# working.net
KiCad netlist of a schematic drawn in EAGLE
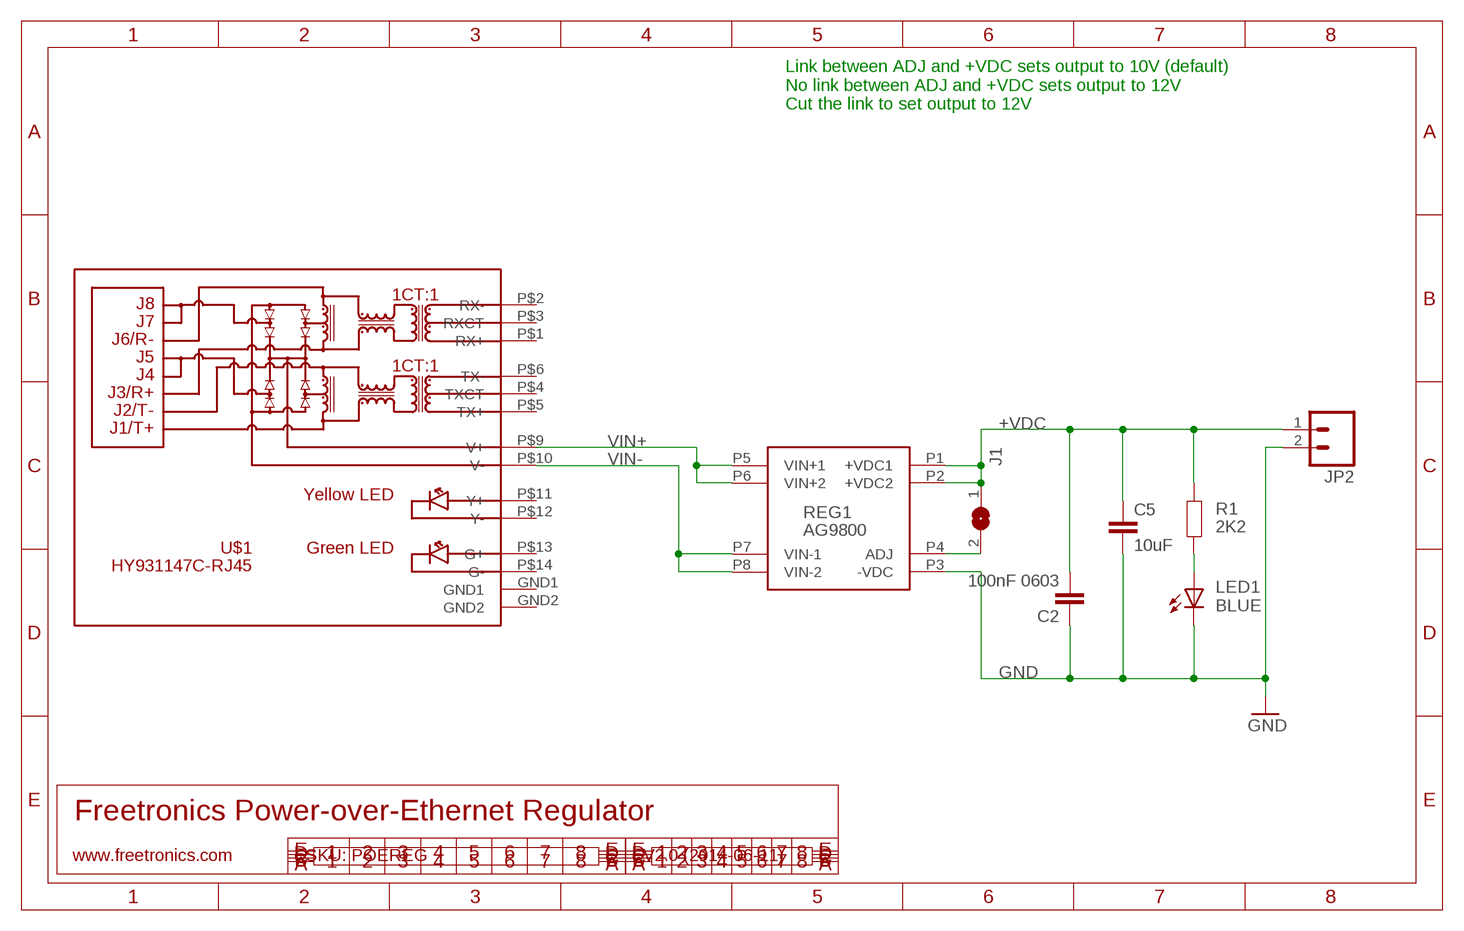
[diagram p0: schematic, sheet 1]

(export (version "E")
  (design (tool "Eeschema 10.0.6"))
  (components
    (comp (ref "C2")
      (value "100nF 0603")
      (footprint "eagle-import:0603")
      (libsource (lib "eagle-import") (part "CAP0603"))
    )
    (comp (ref "C5")
      (value "10uF")
      (footprint "eagle-import:C1206")
      (libsource (lib "eagle-import") (part "C-EUC1206"))
    )
    (comp (ref "J1")
      (value "SJN")
      (footprint "eagle-import:SJ")
      (libsource (lib "eagle-import") (part "SJN"))
    )
    (comp (ref "JP2")
      (value "M025MM")
      (footprint "eagle-import:SCREWTERMINAL-5MM-2")
      (libsource (lib "eagle-import") (part "M025MM"))
    )
    (comp (ref "LED1")
      (value "BLUE")
      (footprint "eagle-import:LED-0603")
      (libsource (lib "eagle-import") (part "LED0603"))
    )
    (comp (ref "R1")
      (value "2K2")
      (footprint "eagle-import:0603")
      (libsource (lib "eagle-import") (part "RESISTOR0603"))
    )
    (comp (ref "REG1")
      (value "AG9800")
      (footprint "eagle-import:AG9800")
      (libsource (lib "eagle-import") (part "AG9800"))
    )
    (comp (ref "U$1")
      (value "HY931147C-RJ45")
      (footprint "eagle-import:HY931147C")
      (libsource (lib "eagle-import") (part "HY931147C-RJ45"))
    )
  )
  (nets
    (net (code "1") (name "/+VDC") (class "Default")
      (node (ref "C2") (pin "2") (pinfunction "2_2") (pintype "passive"))
      (node (ref "C5") (pin "1") (pinfunction "1_1") (pintype "passive"))
      (node (ref "J1") (pin "1") (pinfunction "1_1") (pintype "passive"))
      (node (ref "JP2") (pin "1") (pinfunction "1_1") (pintype "passive"))
      (node (ref "R1") (pin "1") (pinfunction "1_1") (pintype "passive"))
      (node (ref "REG1") (pin "P1") (pinfunction "+VDC1_P1") (pintype "bidirectional"))
      (node (ref "REG1") (pin "P2") (pinfunction "+VDC2_P2") (pintype "bidirectional"))
    )
    (net (code "2") (name "/VIN+") (class "Default")
      (node (ref "REG1") (pin "P5") (pinfunction "VIN+1_P5") (pintype "power_in"))
      (node (ref "REG1") (pin "P6") (pinfunction "VIN+2_P6") (pintype "power_in"))
      (node (ref "U$1") (pin "P$9") (pinfunction "V+_P$9") (pintype "bidirectional"))
    )
    (net (code "3") (name "/VIN-") (class "Default")
      (node (ref "REG1") (pin "P7") (pinfunction "VIN-1_P7") (pintype "power_in"))
      (node (ref "REG1") (pin "P8") (pinfunction "VIN-2_P8") (pintype "power_in"))
      (node (ref "U$1") (pin "P$10") (pinfunction "V-_P$10") (pintype "bidirectional"))
    )
    (net (code "4") (name "GND") (class "Default")
      (node (ref "C2") (pin "1") (pinfunction "1_1") (pintype "passive"))
      (node (ref "C5") (pin "2") (pinfunction "2_2") (pintype "passive"))
      (node (ref "JP2") (pin "2") (pinfunction "2_2") (pintype "passive"))
      (node (ref "LED1") (pin "C") (pinfunction "C_C") (pintype "passive"))
      (node (ref "REG1") (pin "P3") (pinfunction "-VDC_P3") (pintype "bidirectional"))
    )
    (net (code "5") (name "Net-(LED1-PadA)") (class "Default")
      (node (ref "LED1") (pin "A") (pinfunction "A_A") (pintype "passive"))
      (node (ref "R1") (pin "2") (pinfunction "2_2") (pintype "passive"))
    )
    (net (code "6") (name "Net-(REG1-ADJ)") (class "Default")
      (node (ref "J1") (pin "2") (pinfunction "2_2") (pintype "passive"))
      (node (ref "REG1") (pin "P4") (pinfunction "ADJ_P4") (pintype "input"))
    )
    (net (code "7") (name "unconnected-(U$1-G+-PadP$13)") (class "Default")
      (node (ref "U$1") (pin "P$13") (pinfunction "G+_P$13") (pintype "bidirectional"))
    )
    (net (code "8") (name "unconnected-(U$1-G--PadP$14)") (class "Default")
      (node (ref "U$1") (pin "P$14") (pinfunction "G-_P$14") (pintype "bidirectional"))
    )
    (net (code "9") (name "unconnected-(U$1-PadGND1)") (class "Default")
      (node (ref "U$1") (pin "GND1") (pinfunction "GND1_GND1") (pintype "bidirectional"))
    )
    (net (code "10") (name "unconnected-(U$1-PadGND2)") (class "Default")
      (node (ref "U$1") (pin "GND2") (pinfunction "GND2_GND2") (pintype "bidirectional"))
    )
    (net (code "11") (name "unconnected-(U$1-RX+-PadP$1)") (class "Default")
      (node (ref "U$1") (pin "P$1") (pinfunction "RX+_P$1") (pintype "bidirectional"))
    )
    (net (code "12") (name "unconnected-(U$1-RX--PadP$2)") (class "Default")
      (node (ref "U$1") (pin "P$2") (pinfunction "RX-_P$2") (pintype "bidirectional"))
    )
    (net (code "13") (name "unconnected-(U$1-RXCT-PadP$3)") (class "Default")
      (node (ref "U$1") (pin "P$3") (pinfunction "RXCT_P$3") (pintype "bidirectional"))
    )
    (net (code "14") (name "unconnected-(U$1-TX+-PadP$5)") (class "Default")
      (node (ref "U$1") (pin "P$5") (pinfunction "TX+_P$5") (pintype "bidirectional"))
    )
    (net (code "15") (name "unconnected-(U$1-TX--PadP$6)") (class "Default")
      (node (ref "U$1") (pin "P$6") (pinfunction "TX-_P$6") (pintype "bidirectional"))
    )
    (net (code "16") (name "unconnected-(U$1-TXCT-PadP$4)") (class "Default")
      (node (ref "U$1") (pin "P$4") (pinfunction "TXCT_P$4") (pintype "bidirectional"))
    )
    (net (code "17") (name "unconnected-(U$1-Y+-PadP$11)") (class "Default")
      (node (ref "U$1") (pin "P$11") (pinfunction "Y+_P$11") (pintype "bidirectional"))
    )
    (net (code "18") (name "unconnected-(U$1-Y--PadP$12)") (class "Default")
      (node (ref "U$1") (pin "P$12") (pinfunction "Y-_P$12") (pintype "bidirectional"))
    )
  )
)
